# design.net
KiCad netlist of a schematic drawn in Altium Designer
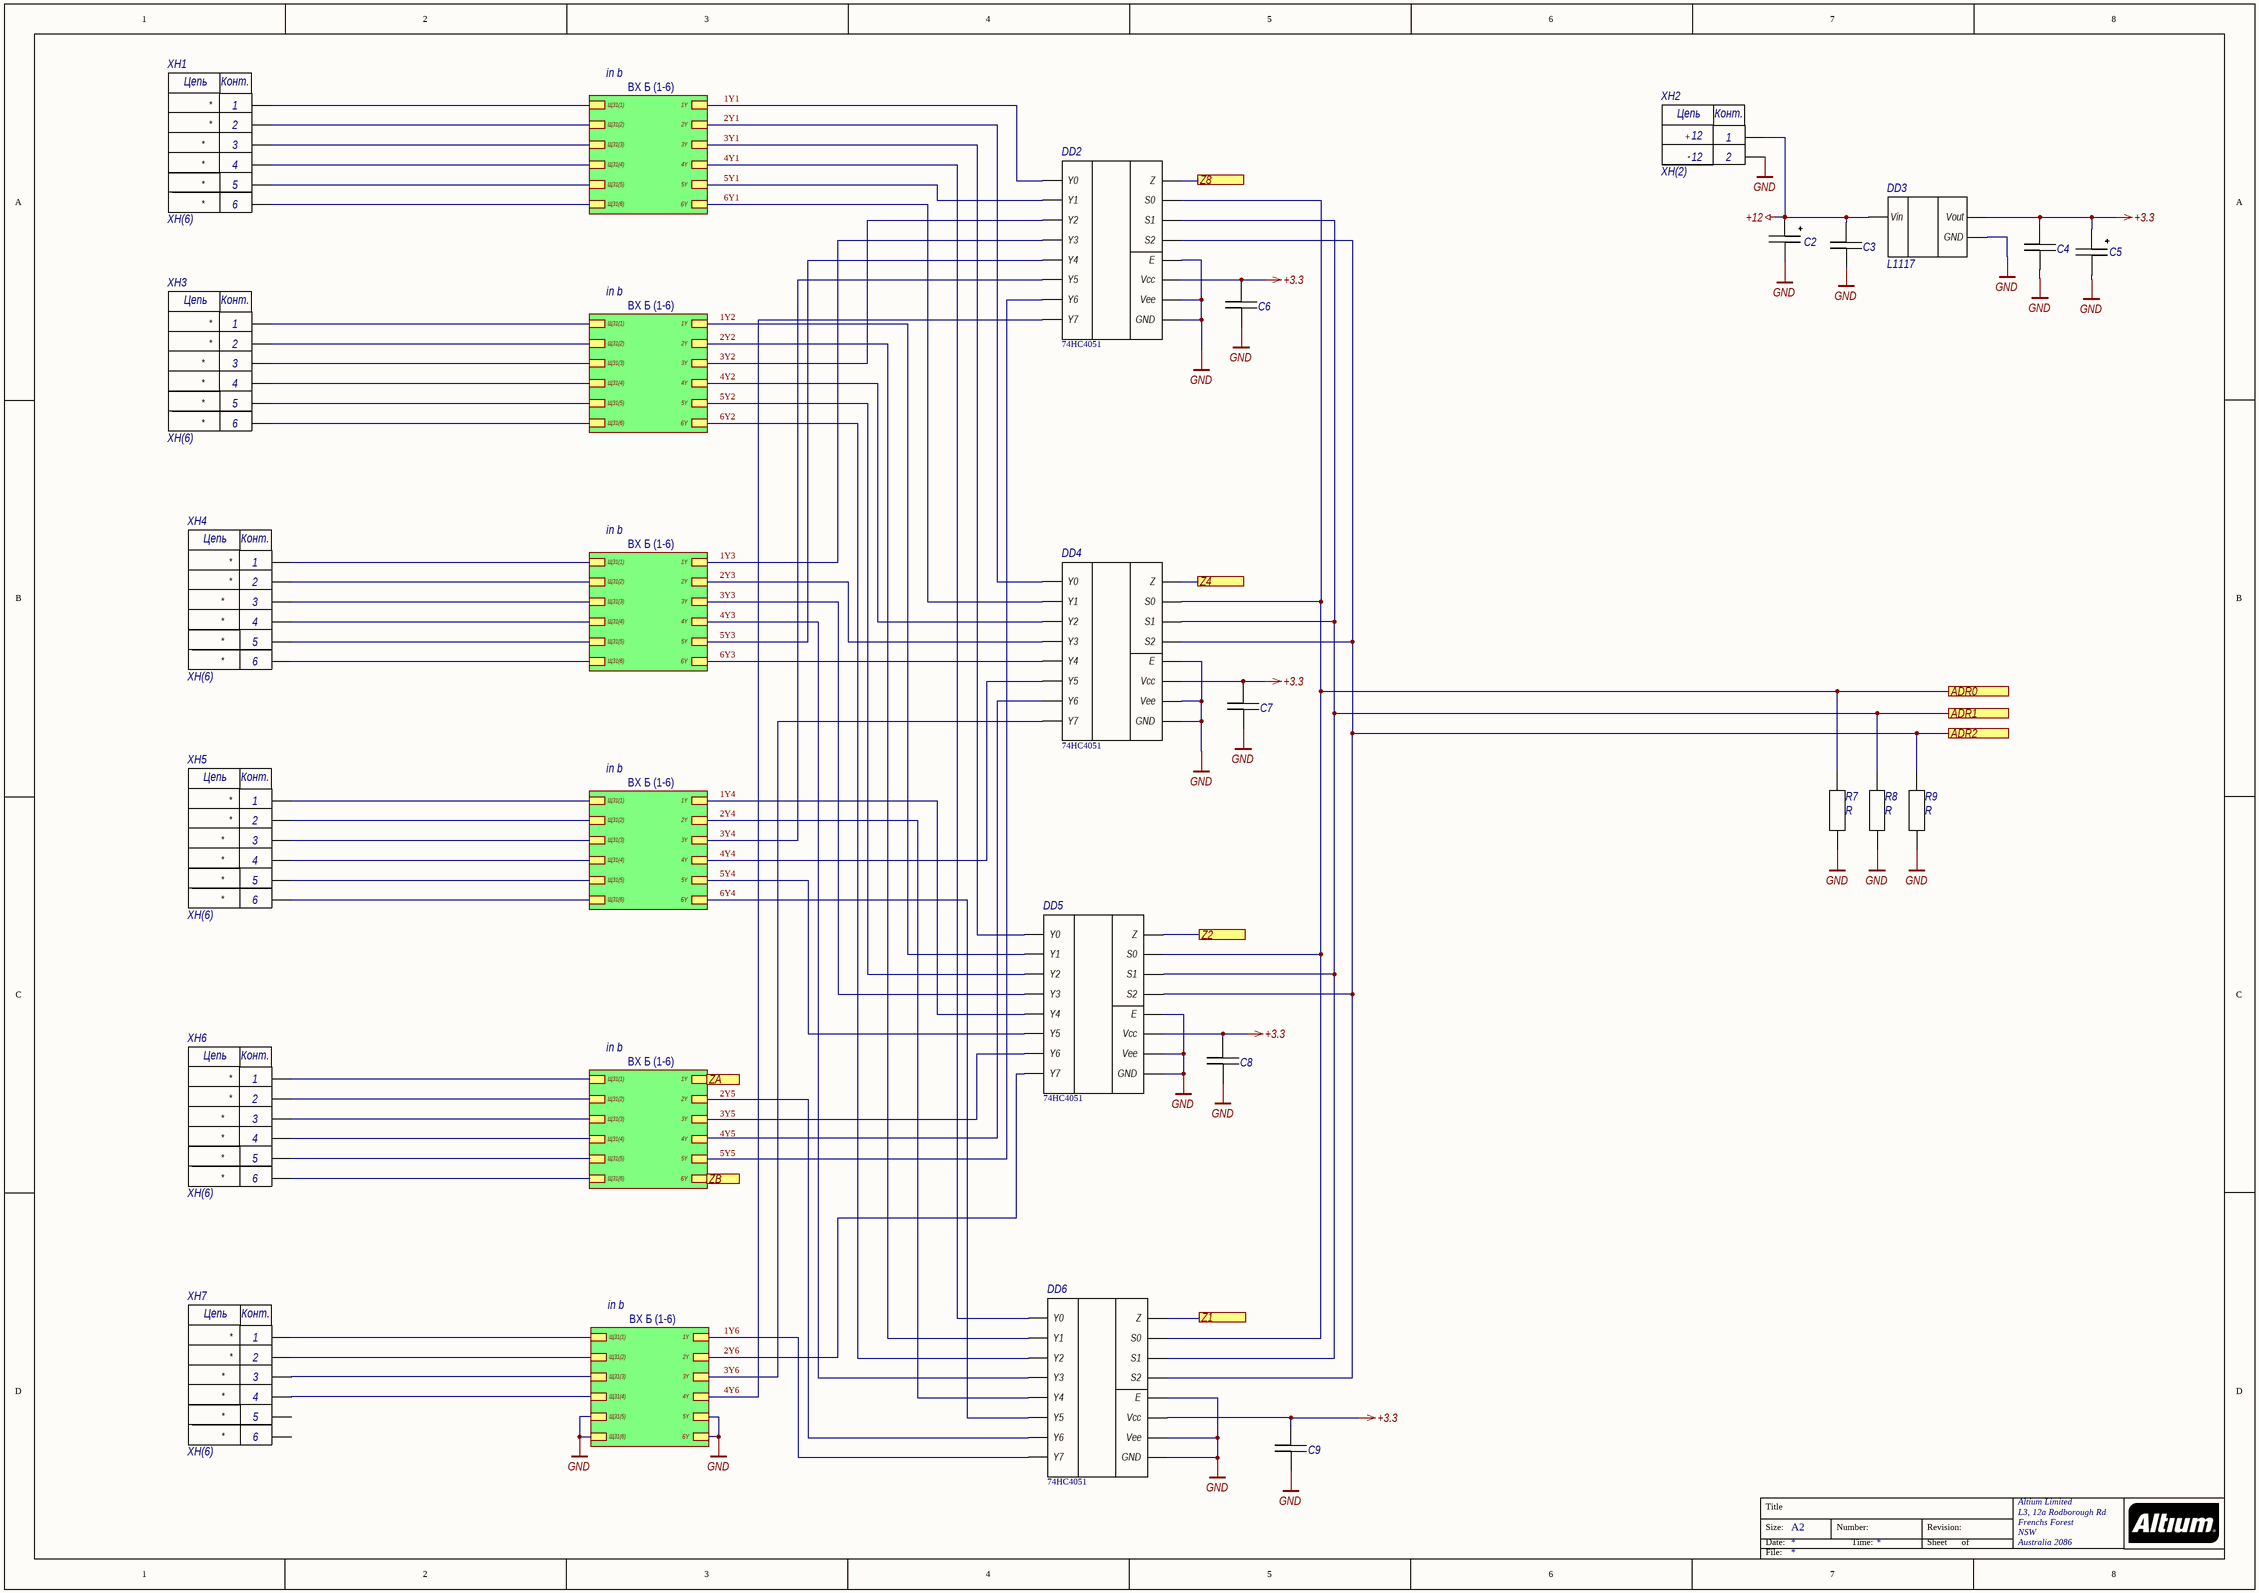
[diagram p0: СОГЛАСОВАНИЕ — копия.SchDoc]

(export (version "E")
  (design (tool "Eeschema 10.0.6"))
  (components
    (comp (ref "C2") (value "C(AlEL)") (footprint "C(AlEL)") (libsource (lib "UGO") (part "C(AlEL)")))
    (comp (ref "C3")
      (value "C(ceramic)")
      (footprint "C(ceramic)")
      (libsource (lib "UGO") (part "C(ceramic)"))
    )
    (comp (ref "C4")
      (value "C(ceramic)")
      (footprint "C(ceramic)")
      (libsource (lib "UGO") (part "C(ceramic)"))
    )
    (comp (ref "C5") (value "C(AlEL)") (footprint "C(AlEL)") (libsource (lib "UGO") (part "C(AlEL)")))
    (comp (ref "C6")
      (value "C(ceramic)")
      (footprint "C(ceramic)")
      (libsource (lib "UGO") (part "C(ceramic)"))
    )
    (comp (ref "C7")
      (value "C(ceramic)")
      (footprint "C(ceramic)")
      (libsource (lib "UGO") (part "C(ceramic)"))
    )
    (comp (ref "C8")
      (value "C(ceramic)")
      (footprint "C(ceramic)")
      (libsource (lib "UGO") (part "C(ceramic)"))
    )
    (comp (ref "C9")
      (value "C(ceramic)")
      (footprint "C(ceramic)")
      (libsource (lib "UGO") (part "C(ceramic)"))
    )
    (comp (ref "DD2") (value "74HC4051") (footprint "74HC4050(51)") (libsource (lib "UGO") (part "74HC4051")))
    (comp (ref "DD3") (value "L1117") (footprint "LDL1117") (libsource (lib "UGO") (part "LDL1117")))
    (comp (ref "DD4") (value "74HC4051") (footprint "74HC4050(51)") (libsource (lib "UGO") (part "74HC4051")))
    (comp (ref "DD5") (value "74HC4051") (footprint "74HC4050(51)") (libsource (lib "UGO") (part "74HC4051")))
    (comp (ref "DD6") (value "74HC4051") (footprint "74HC4050(51)") (libsource (lib "UGO") (part "74HC4051")))
    (comp (ref "R7") (value "R") (footprint "R") (libsource (lib "UGO") (part "R")))
    (comp (ref "R8") (value "R") (footprint "R") (libsource (lib "UGO") (part "R")))
    (comp (ref "R9") (value "R") (footprint "R") (libsource (lib "UGO") (part "R")))
    (comp (ref "XH1") (value "ХH(6)") (footprint "XH(6)") (libsource (lib "UGO") (part "ХH(6)")))
    (comp (ref "XH2") (value "ХН(2)") (footprint "ХН(2)") (libsource (lib "UGO") (part "ХН(2)")))
    (comp (ref "XH3") (value "ХH(6)") (footprint "XH(6)") (libsource (lib "UGO") (part "ХH(6)")))
    (comp (ref "XH4") (value "ХH(6)") (footprint "XH(6)") (libsource (lib "UGO") (part "ХH(6)")))
    (comp (ref "XH5") (value "ХH(6)") (footprint "XH(6)") (libsource (lib "UGO") (part "ХH(6)")))
    (comp (ref "XH6") (value "ХH(6)") (footprint "XH(6)") (libsource (lib "UGO") (part "ХH(6)")))
    (comp (ref "XH7") (value "ХH(6)") (footprint "XH(6)") (libsource (lib "UGO") (part "ХH(6)")))
  )
  (nets
    (net (code "1") (name "+3.3") (class "Default")
      (node (ref "C4") (pin "2") (pintype "passive"))
      (node (ref "C5") (pin "1") (pintype "passive"))
      (node (ref "C6") (pin "2") (pintype "passive"))
      (node (ref "C7") (pin "2") (pintype "passive"))
      (node (ref "C8") (pin "2") (pintype "passive"))
      (node (ref "C9") (pin "2") (pintype "passive"))
      (node (ref "DD2") (pin "16") (pinfunction "Vcc_16") (pintype "passive"))
      (node (ref "DD3") (pin "2") (pinfunction "Vout_2") (pintype "passive"))
      (node (ref "DD4") (pin "16") (pinfunction "Vcc_16") (pintype "passive"))
      (node (ref "DD5") (pin "16") (pinfunction "Vcc_16") (pintype "passive"))
      (node (ref "DD6") (pin "16") (pinfunction "Vcc_16") (pintype "passive"))
    )
    (net (code "2") (name "+12") (class "Default")
      (node (ref "C2") (pin "1") (pintype "passive"))
      (node (ref "C3") (pin "2") (pintype "passive"))
      (node (ref "DD3") (pin "3") (pinfunction "Vin_3") (pintype "passive"))
      (node (ref "XH2") (pin "1") (pinfunction "+_1") (pintype "passive"))
    )
    (net (code "3") (name "/1Y1") (class "Default")
      (node (ref "DD2") (pin "13") (pinfunction "Y0_13") (pintype "passive"))
    )
    (net (code "4") (name "/1Y2") (class "Default")
      (node (ref "DD5") (pin "14") (pinfunction "Y1_14") (pintype "passive"))
    )
    (net (code "5") (name "/1Y3") (class "Default")
      (node (ref "DD2") (pin "12") (pinfunction "Y3_12") (pintype "passive"))
    )
    (net (code "6") (name "/1Y4") (class "Default")
      (node (ref "DD5") (pin "1") (pinfunction "Y4_1") (pintype "passive"))
    )
    (net (code "7") (name "/1Y6") (class "Default")
      (node (ref "DD6") (pin "4") (pinfunction "Y7_4") (pintype "passive"))
    )
    (net (code "8") (name "/2Y") (class "Default")
      (node (ref "DD6") (pin "2") (pinfunction "Y6_2") (pintype "passive"))
    )
    (net (code "9") (name "/2Y1") (class "Default")
      (node (ref "DD4") (pin "13") (pinfunction "Y0_13") (pintype "passive"))
    )
    (net (code "10") (name "/2Y2") (class "Default")
      (node (ref "DD6") (pin "14") (pinfunction "Y1_14") (pintype "passive"))
    )
    (net (code "11") (name "/2Y3") (class "Default")
      (node (ref "DD4") (pin "12") (pinfunction "Y3_12") (pintype "passive"))
    )
    (net (code "12") (name "/2Y4") (class "Default")
      (node (ref "DD6") (pin "1") (pinfunction "Y4_1") (pintype "passive"))
    )
    (net (code "14") (name "/2Y6") (class "Default")
      (node (ref "DD5") (pin "4") (pinfunction "Y7_4") (pintype "passive"))
    )
    (net (code "15") (name "/3Y") (class "Default")
      (node (ref "DD5") (pin "2") (pinfunction "Y6_2") (pintype "passive"))
    )
    (net (code "16") (name "/3Y1") (class "Default")
      (node (ref "DD5") (pin "13") (pinfunction "Y0_13") (pintype "passive"))
    )
    (net (code "17") (name "/3Y2") (class "Default")
      (node (ref "DD2") (pin "15") (pinfunction "Y2_15") (pintype "passive"))
    )
    (net (code "18") (name "/3Y3") (class "Default")
      (node (ref "DD5") (pin "12") (pinfunction "Y3_12") (pintype "passive"))
    )
    (net (code "19") (name "/3Y4") (class "Default")
      (node (ref "DD2") (pin "5") (pinfunction "Y5_5") (pintype "passive"))
    )
    (net (code "21") (name "/3Y6") (class "Default")
      (node (ref "DD4") (pin "4") (pinfunction "Y7_4") (pintype "passive"))
    )
    (net (code "22") (name "/4Y") (class "Default")
      (node (ref "DD4") (pin "2") (pinfunction "Y6_2") (pintype "passive"))
    )
    (net (code "23") (name "/4Y1") (class "Default")
      (node (ref "DD6") (pin "13") (pinfunction "Y0_13") (pintype "passive"))
    )
    (net (code "24") (name "/4Y2") (class "Default")
      (node (ref "DD4") (pin "15") (pinfunction "Y2_15") (pintype "passive"))
    )
    (net (code "25") (name "/4Y3") (class "Default")
      (node (ref "DD6") (pin "12") (pinfunction "Y3_12") (pintype "passive"))
    )
    (net (code "26") (name "/4Y4") (class "Default")
      (node (ref "DD4") (pin "5") (pinfunction "Y5_5") (pintype "passive"))
    )
    (net (code "28") (name "/4Y6") (class "Default")
      (node (ref "DD2") (pin "4") (pinfunction "Y7_4") (pintype "passive"))
    )
    (net (code "29") (name "/5Y") (class "Default")
      (node (ref "DD2") (pin "2") (pinfunction "Y6_2") (pintype "passive"))
    )
    (net (code "30") (name "/5Y1") (class "Default")
      (node (ref "DD2") (pin "14") (pinfunction "Y1_14") (pintype "passive"))
    )
    (net (code "31") (name "/5Y2") (class "Default")
      (node (ref "DD5") (pin "15") (pinfunction "Y2_15") (pintype "passive"))
    )
    (net (code "32") (name "/5Y3") (class "Default")
      (node (ref "DD2") (pin "1") (pinfunction "Y4_1") (pintype "passive"))
    )
    (net (code "33") (name "/5Y4") (class "Default")
      (node (ref "DD5") (pin "5") (pinfunction "Y5_5") (pintype "passive"))
    )
    (net (code "35") (name "/6Y1") (class "Default")
      (node (ref "DD4") (pin "14") (pinfunction "Y1_14") (pintype "passive"))
    )
    (net (code "36") (name "/6Y2") (class "Default")
      (node (ref "DD6") (pin "15") (pinfunction "Y2_15") (pintype "passive"))
    )
    (net (code "37") (name "/6Y3") (class "Default")
      (node (ref "DD4") (pin "1") (pinfunction "Y4_1") (pintype "passive"))
    )
    (net (code "38") (name "/6Y4") (class "Default")
      (node (ref "DD6") (pin "5") (pinfunction "Y5_5") (pintype "passive"))
    )
    (net (code "39") (name "/ADR0") (class "Default")
      (node (ref "DD2") (pin "11") (pinfunction "S0_11") (pintype "passive"))
      (node (ref "DD4") (pin "11") (pinfunction "S0_11") (pintype "passive"))
      (node (ref "DD5") (pin "11") (pinfunction "S0_11") (pintype "passive"))
      (node (ref "DD6") (pin "11") (pinfunction "S0_11") (pintype "passive"))
      (node (ref "R7") (pin "2") (pintype "passive"))
    )
    (net (code "40") (name "/ADR1") (class "Default")
      (node (ref "DD2") (pin "10") (pinfunction "S1_10") (pintype "passive"))
      (node (ref "DD4") (pin "10") (pinfunction "S1_10") (pintype "passive"))
      (node (ref "DD5") (pin "10") (pinfunction "S1_10") (pintype "passive"))
      (node (ref "DD6") (pin "10") (pinfunction "S1_10") (pintype "passive"))
      (node (ref "R8") (pin "2") (pintype "passive"))
    )
    (net (code "41") (name "/ADR2") (class "Default")
      (node (ref "DD2") (pin "9") (pinfunction "S2_9") (pintype "passive"))
      (node (ref "DD4") (pin "9") (pinfunction "S2_9") (pintype "passive"))
      (node (ref "DD5") (pin "9") (pinfunction "S2_9") (pintype "passive"))
      (node (ref "DD6") (pin "9") (pinfunction "S2_9") (pintype "passive"))
      (node (ref "R9") (pin "2") (pintype "passive"))
    )
    (net (code "42") (name "/Z1") (class "Default")
      (node (ref "DD6") (pin "3") (pinfunction "Z_3") (pintype "passive"))
    )
    (net (code "43") (name "/Z2") (class "Default")
      (node (ref "DD5") (pin "3") (pinfunction "Z_3") (pintype "passive"))
    )
    (net (code "44") (name "/Z4") (class "Default")
      (node (ref "DD4") (pin "3") (pinfunction "Z_3") (pintype "passive"))
    )
    (net (code "45") (name "/Z8") (class "Default")
      (node (ref "DD2") (pin "3") (pinfunction "Z_3") (pintype "passive"))
    )
    (net (code "48") (name "/Щ31(1)") (class "Default")
      (node (ref "XH3") (pin "1") (pinfunction "*_1") (pintype "passive"))
    )
    (net (code "49") (name "/Щ31(1)_1") (class "Default")
      (node (ref "XH6") (pin "1") (pinfunction "*_1") (pintype "passive"))
    )
    (net (code "50") (name "/Щ31(1)_2") (class "Default")
      (node (ref "XH4") (pin "1") (pinfunction "*_1") (pintype "passive"))
    )
    (net (code "51") (name "/Щ31(1)_3") (class "Default")
      (node (ref "XH5") (pin "1") (pinfunction "*_1") (pintype "passive"))
    )
    (net (code "52") (name "/Щ31(1)_4") (class "Default")
      (node (ref "XH7") (pin "1") (pinfunction "*_1") (pintype "passive"))
    )
    (net (code "53") (name "/Щ31(1)_5") (class "Default")
      (node (ref "XH1") (pin "1") (pinfunction "*_1") (pintype "passive"))
    )
    (net (code "54") (name "/Щ31(2)") (class "Default")
      (node (ref "XH3") (pin "2") (pinfunction "*_2") (pintype "passive"))
    )
    (net (code "55") (name "/Щ31(2)_1") (class "Default")
      (node (ref "XH6") (pin "2") (pinfunction "*_2") (pintype "passive"))
    )
    (net (code "56") (name "/Щ31(2)_2") (class "Default")
      (node (ref "XH4") (pin "2") (pinfunction "*_2") (pintype "passive"))
    )
    (net (code "57") (name "/Щ31(2)_3") (class "Default")
      (node (ref "XH5") (pin "2") (pinfunction "*_2") (pintype "passive"))
    )
    (net (code "58") (name "/Щ31(2)_4") (class "Default")
      (node (ref "XH7") (pin "2") (pinfunction "*_2") (pintype "passive"))
    )
    (net (code "59") (name "/Щ31(2)_5") (class "Default")
      (node (ref "XH1") (pin "2") (pinfunction "*_2") (pintype "passive"))
    )
    (net (code "60") (name "/Щ31(3)") (class "Default")
      (node (ref "XH3") (pin "3") (pinfunction "*_3") (pintype "passive"))
    )
    (net (code "61") (name "/Щ31(3)_1") (class "Default")
      (node (ref "XH6") (pin "3") (pinfunction "*_3") (pintype "passive"))
    )
    (net (code "62") (name "/Щ31(3)_2") (class "Default")
      (node (ref "XH4") (pin "3") (pinfunction "*_3") (pintype "passive"))
    )
    (net (code "63") (name "/Щ31(3)_3") (class "Default")
      (node (ref "XH5") (pin "3") (pinfunction "*_3") (pintype "passive"))
    )
    (net (code "64") (name "/Щ31(3)_4") (class "Default")
      (node (ref "XH7") (pin "3") (pinfunction "*_3") (pintype "passive"))
    )
    (net (code "65") (name "/Щ31(3)_5") (class "Default")
      (node (ref "XH1") (pin "3") (pinfunction "*_3") (pintype "passive"))
    )
    (net (code "66") (name "/Щ31(4)") (class "Default")
      (node (ref "XH3") (pin "4") (pinfunction "*_4") (pintype "passive"))
    )
    (net (code "67") (name "/Щ31(4)_1") (class "Default")
      (node (ref "XH6") (pin "4") (pinfunction "*_4") (pintype "passive"))
    )
    (net (code "68") (name "/Щ31(4)_2") (class "Default")
      (node (ref "XH4") (pin "4") (pinfunction "*_4") (pintype "passive"))
    )
    (net (code "69") (name "/Щ31(4)_3") (class "Default")
      (node (ref "XH5") (pin "4") (pinfunction "*_4") (pintype "passive"))
    )
    (net (code "70") (name "/Щ31(4)_4") (class "Default")
      (node (ref "XH7") (pin "4") (pinfunction "*_4") (pintype "passive"))
    )
    (net (code "71") (name "/Щ31(4)_5") (class "Default")
      (node (ref "XH1") (pin "4") (pinfunction "*_4") (pintype "passive"))
    )
    (net (code "72") (name "/Щ31(5)") (class "Default")
      (node (ref "XH1") (pin "5") (pinfunction "*_5") (pintype "passive"))
    )
    (net (code "73") (name "/Щ31(5)_1") (class "Default")
      (node (ref "XH6") (pin "5") (pinfunction "*_5") (pintype "passive"))
    )
    (net (code "74") (name "/Щ31(5)_2") (class "Default")
      (node (ref "XH3") (pin "5") (pinfunction "*_5") (pintype "passive"))
    )
    (net (code "75") (name "/Щ31(5)_3") (class "Default")
      (node (ref "XH4") (pin "5") (pinfunction "*_5") (pintype "passive"))
    )
    (net (code "76") (name "/Щ31(5)_4") (class "Default")
      (node (ref "XH5") (pin "5") (pinfunction "*_5") (pintype "passive"))
    )
    (net (code "77") (name "/Щ31(6)") (class "Default")
      (node (ref "XH1") (pin "6") (pinfunction "*_6") (pintype "passive"))
    )
    (net (code "78") (name "/Щ31(6)_1") (class "Default")
      (node (ref "XH6") (pin "6") (pinfunction "*_6") (pintype "passive"))
    )
    (net (code "79") (name "/Щ31(6)_2") (class "Default")
      (node (ref "XH3") (pin "6") (pinfunction "*_6") (pintype "passive"))
    )
    (net (code "80") (name "/Щ31(6)_3") (class "Default")
      (node (ref "XH4") (pin "6") (pinfunction "*_6") (pintype "passive"))
    )
    (net (code "81") (name "/Щ31(6)_4") (class "Default")
      (node (ref "XH5") (pin "6") (pinfunction "*_6") (pintype "passive"))
    )
    (net (code "82") (name "GND") (class "Default")
      (node (ref "C2") (pin "2") (pintype "passive"))
      (node (ref "C3") (pin "1") (pintype "passive"))
      (node (ref "C4") (pin "1") (pintype "passive"))
      (node (ref "C5") (pin "2") (pintype "passive"))
      (node (ref "C6") (pin "1") (pintype "passive"))
      (node (ref "C7") (pin "1") (pintype "passive"))
      (node (ref "C8") (pin "1") (pintype "passive"))
      (node (ref "C9") (pin "1") (pintype "passive"))
      (node (ref "DD2") (pin "6") (pinfunction "E_6") (pintype "passive"))
      (node (ref "DD2") (pin "7") (pinfunction "Vee_7") (pintype "passive"))
      (node (ref "DD2") (pin "8") (pinfunction "GND_8") (pintype "passive"))
      (node (ref "DD3") (pin "1") (pinfunction "GND_1") (pintype "passive"))
      (node (ref "DD4") (pin "6") (pinfunction "E_6") (pintype "passive"))
      (node (ref "DD4") (pin "7") (pinfunction "Vee_7") (pintype "passive"))
      (node (ref "DD4") (pin "8") (pinfunction "GND_8") (pintype "passive"))
      (node (ref "DD5") (pin "6") (pinfunction "E_6") (pintype "passive"))
      (node (ref "DD5") (pin "7") (pinfunction "Vee_7") (pintype "passive"))
      (node (ref "DD5") (pin "8") (pinfunction "GND_8") (pintype "passive"))
      (node (ref "DD6") (pin "6") (pinfunction "E_6") (pintype "passive"))
      (node (ref "DD6") (pin "7") (pinfunction "Vee_7") (pintype "passive"))
      (node (ref "DD6") (pin "8") (pinfunction "GND_8") (pintype "passive"))
      (node (ref "R7") (pin "1") (pintype "passive"))
      (node (ref "R8") (pin "1") (pintype "passive"))
      (node (ref "R9") (pin "1") (pintype "passive"))
      (node (ref "XH2") (pin "2") (pinfunction "-_2") (pintype "passive"))
    )
    (net (code "83") (name "unconnected-(XH7-*-Pad5)") (class "Default")
      (node (ref "XH7") (pin "5") (pinfunction "*_5") (pintype "passive"))
    )
    (net (code "84") (name "unconnected-(XH7-*-Pad6)") (class "Default")
      (node (ref "XH7") (pin "6") (pinfunction "*_6") (pintype "passive"))
    )
  )
)
